# INTech_-_Carte_de_Base.net
KiCad netlist of a schematic drawn in EAGLE
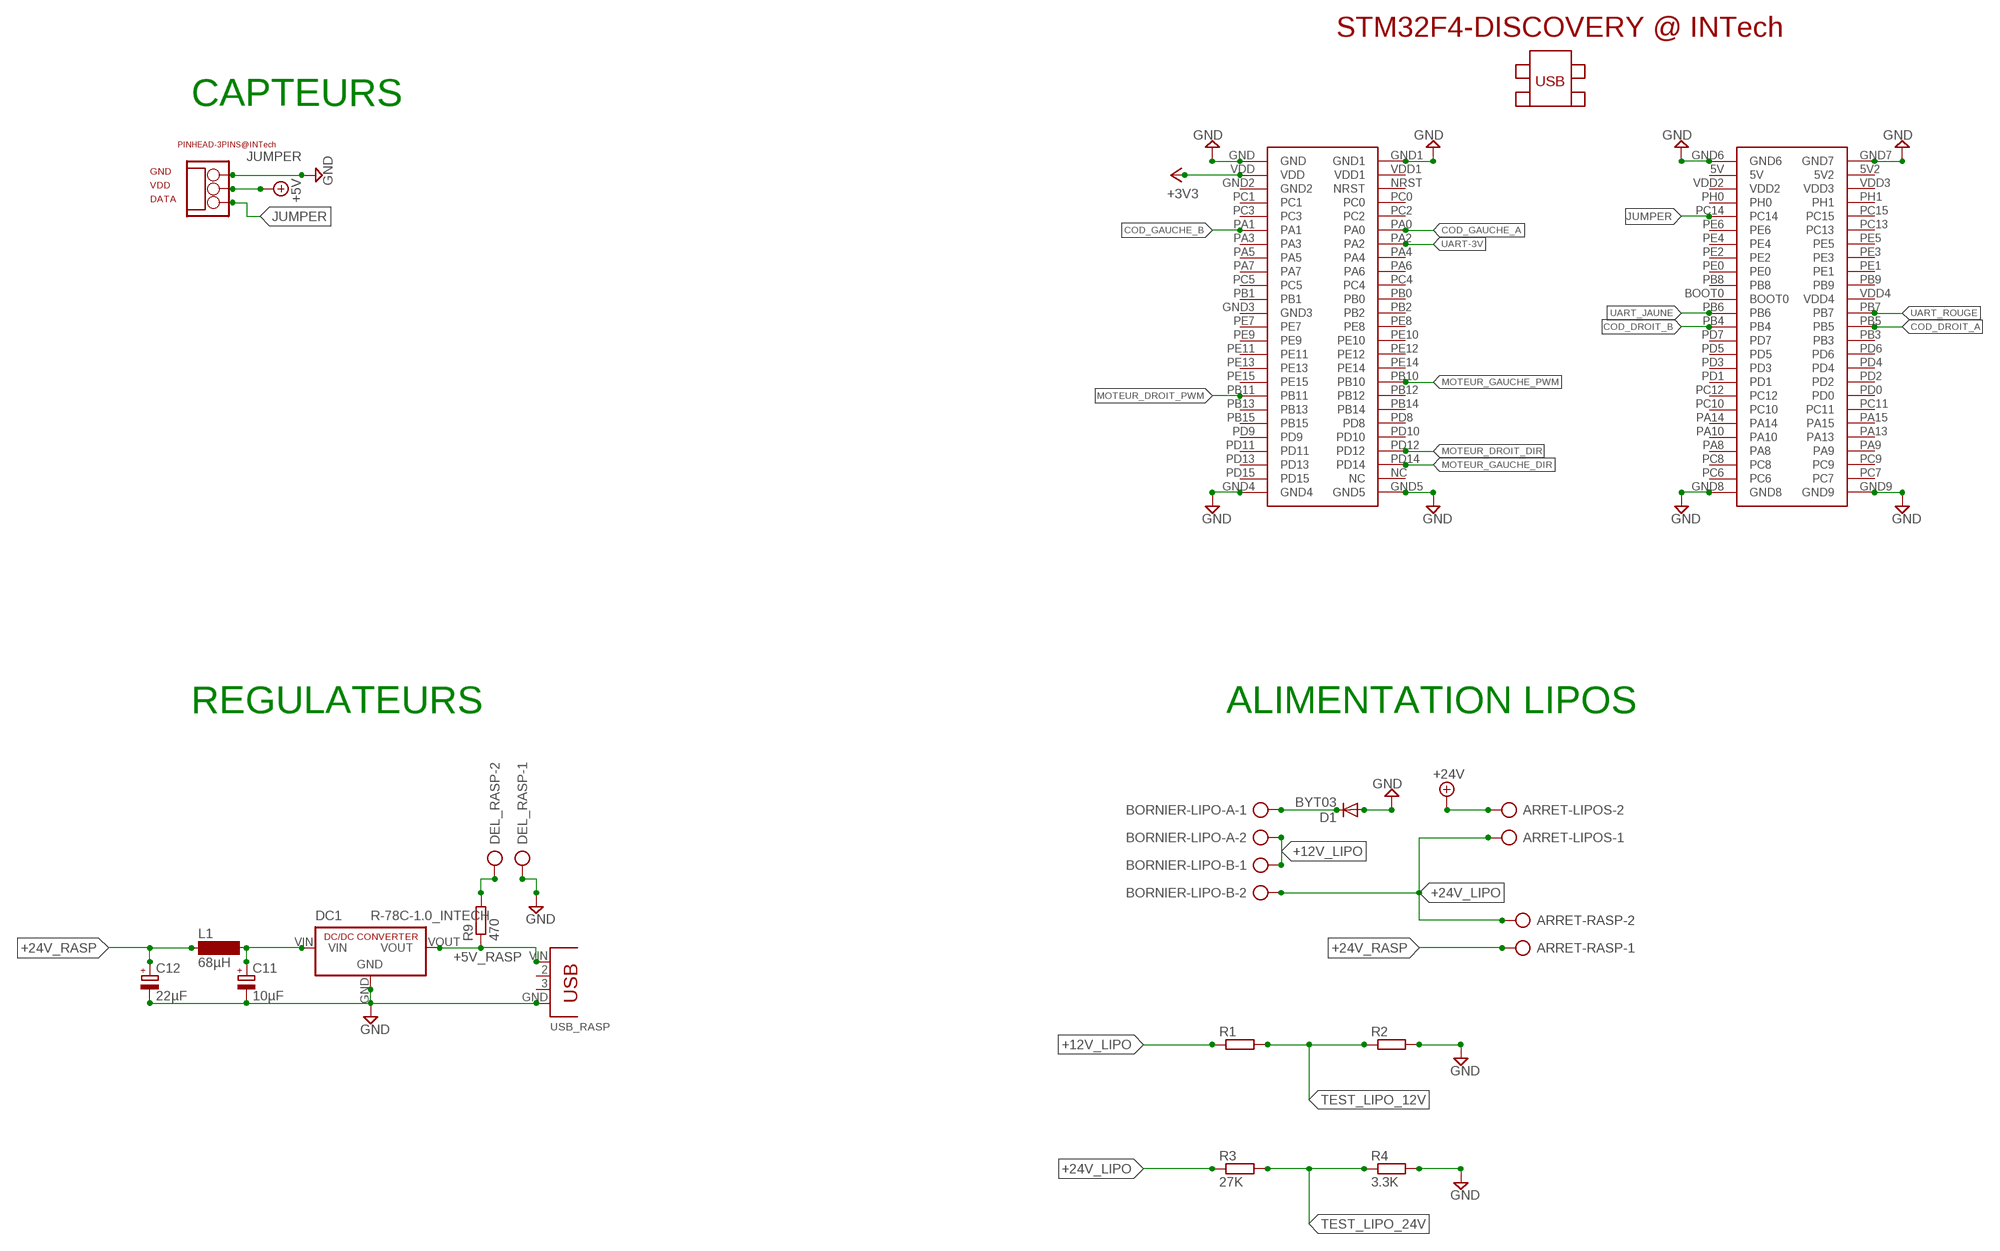
[diagram p0: schematic, sheet 1, part 1 of 2]
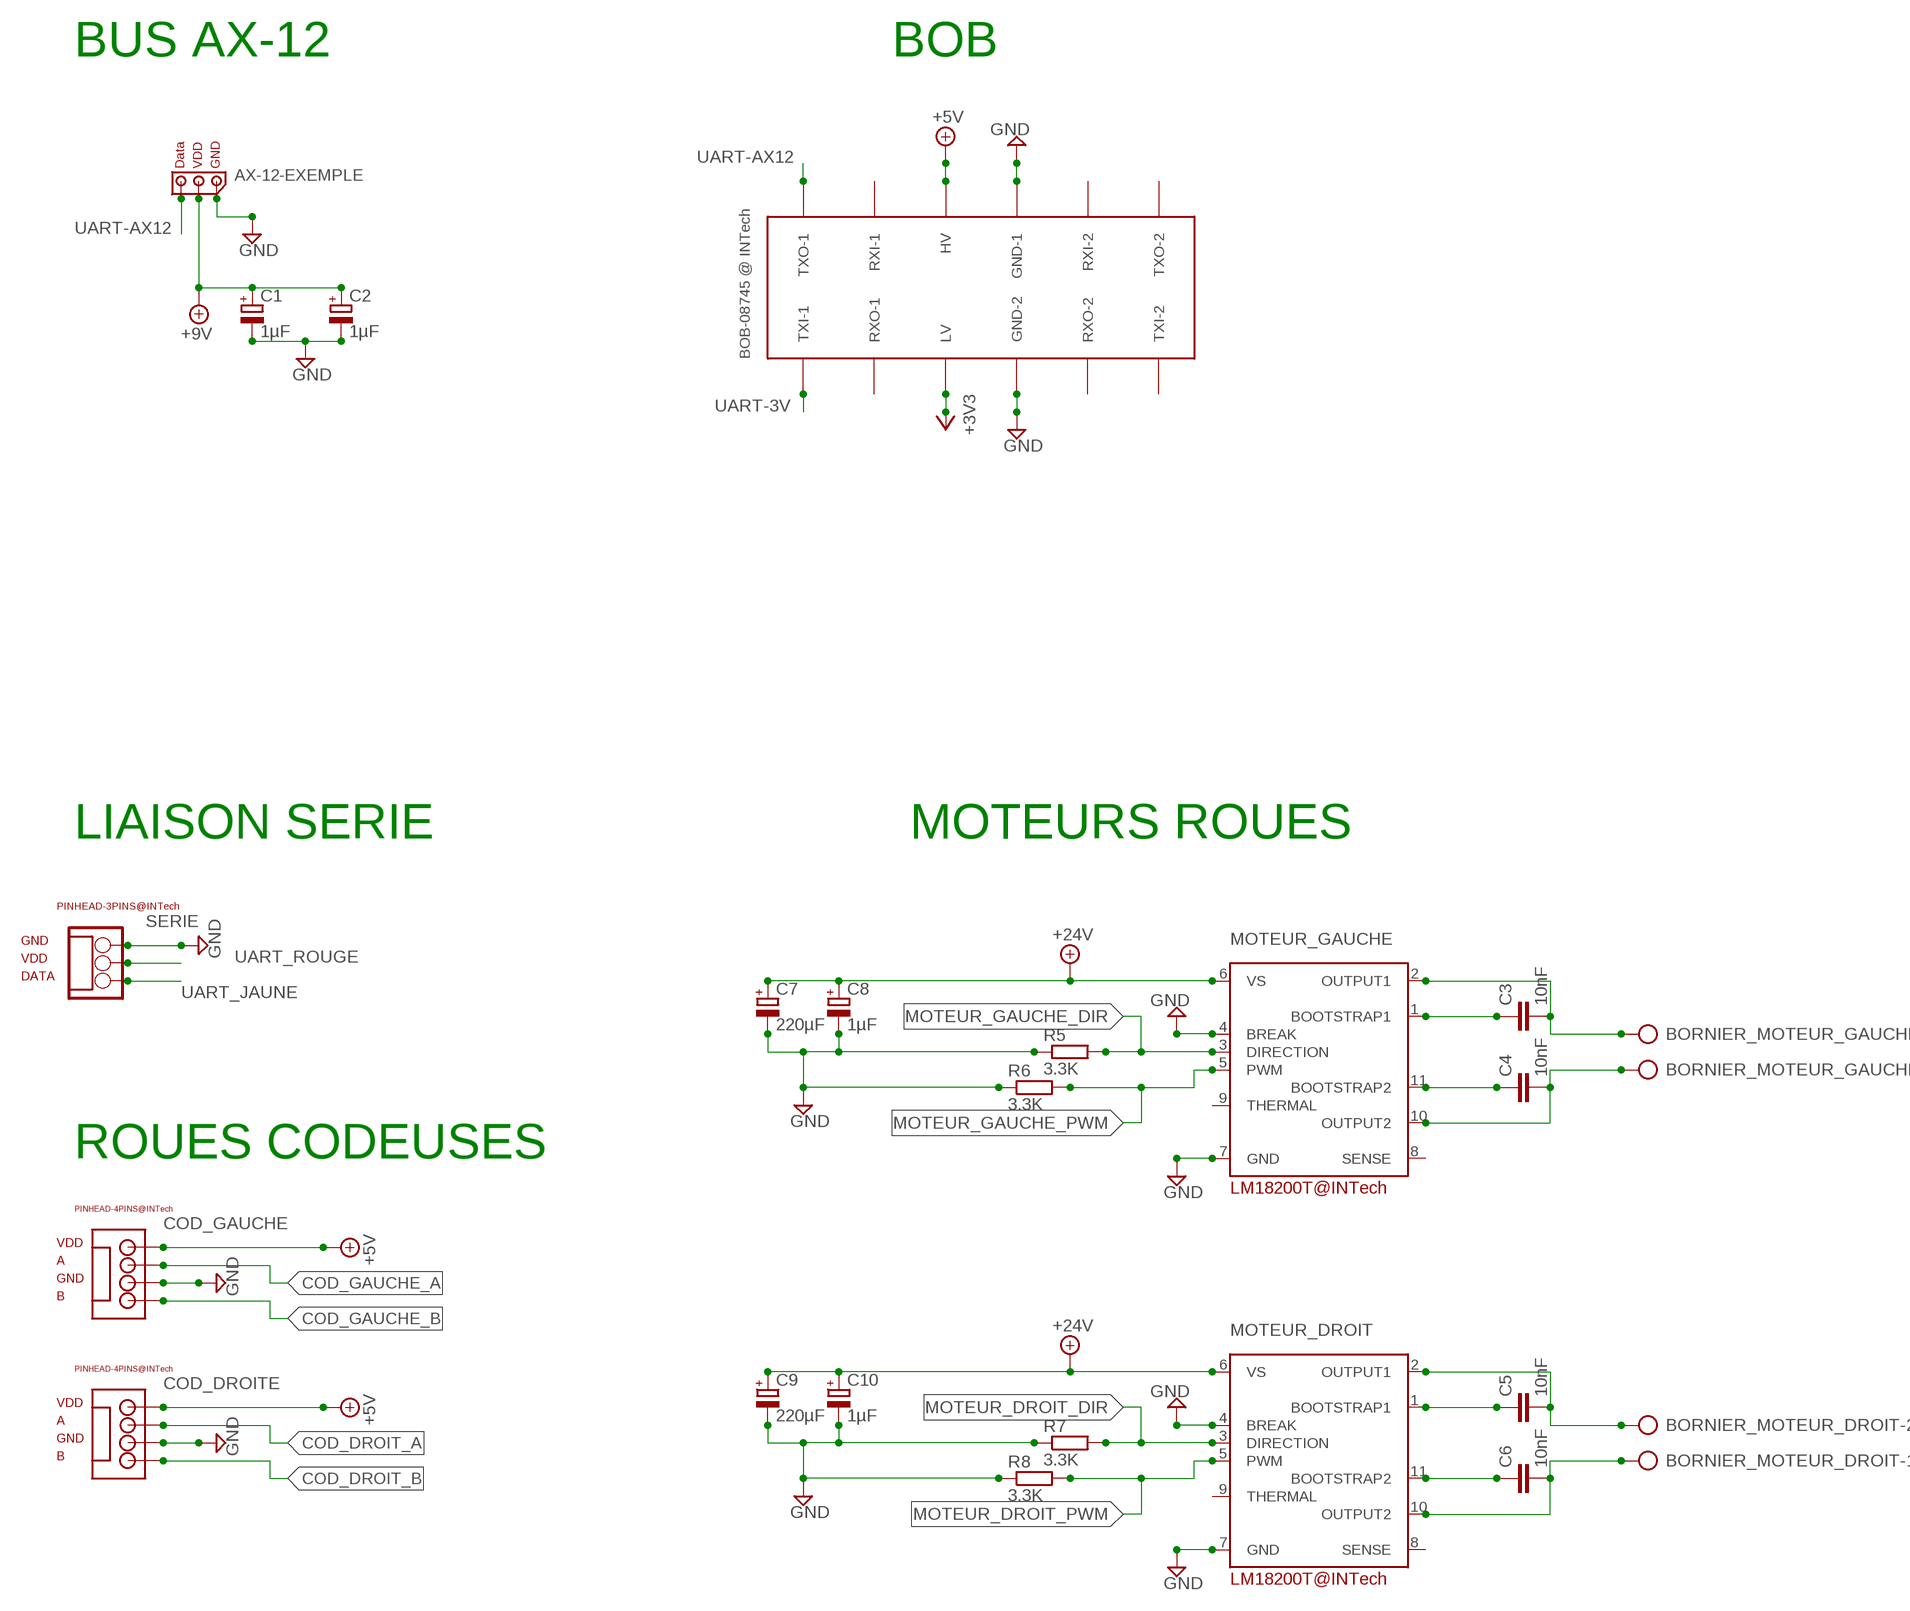
[diagram p1: schematic, sheet 1, part 2 of 2]

(export (version "E")
  (design (tool "Eeschema 10.0.6"))
  (components
    (comp (ref "ARRET-LIPOS")
      (value "AK300/2")
      (footprint "eagle-import:AK300_2")
      (libsource (lib "eagle-import") (part "AK300/2"))
    )
    (comp (ref "ARRET-RASP")
      (value "AK300/2")
      (footprint "eagle-import:AK300_2")
      (libsource (lib "eagle-import") (part "AK300/2"))
    )
    (comp (ref "AX-12-EXEMPLE")
      (value "AX-12_CF_INTECH")
      (footprint "eagle-import:AX-12_CF_INTECH")
      (libsource (lib "eagle-import") (part "AX-12_CF_INTECH"))
    )
    (comp (ref "BORNIER-LIPO-A")
      (value "AK300/2")
      (footprint "eagle-import:AK300_2")
      (libsource (lib "eagle-import") (part "AK300/2"))
    )
    (comp (ref "BORNIER-LIPO-B")
      (value "AK300/2")
      (footprint "eagle-import:AK300_2")
      (libsource (lib "eagle-import") (part "AK300/2"))
    )
    (comp (ref "BORNIER_MOTEUR_DROIT")
      (value "AK300/2")
      (footprint "eagle-import:AK300_2")
      (libsource (lib "eagle-import") (part "AK300/2"))
    )
    (comp (ref "BORNIER_MOTEUR_GAUCHE")
      (value "AK300/2")
      (footprint "eagle-import:AK300_2")
      (libsource (lib "eagle-import") (part "AK300/2"))
    )
    (comp (ref "C1")
      (value "1µF")
      (footprint "eagle-import:E2,5-6E")
      (libsource (lib "eagle-import") (part "CPOL-EUE2,5-6E"))
    )
    (comp (ref "C2")
      (value "1µF")
      (footprint "eagle-import:E2,5-6E")
      (libsource (lib "eagle-import") (part "CPOL-EUE2,5-6E"))
    )
    (comp (ref "C3")
      (value "10nF")
      (footprint "eagle-import:C050-025X075")
      (libsource (lib "eagle-import") (part "C-EU050-025X075"))
    )
    (comp (ref "C4")
      (value "10nF")
      (footprint "eagle-import:C050-025X075")
      (libsource (lib "eagle-import") (part "C-EU050-025X075"))
    )
    (comp (ref "C5")
      (value "10nF")
      (footprint "eagle-import:C050-025X075")
      (libsource (lib "eagle-import") (part "C-EU050-025X075"))
    )
    (comp (ref "C6")
      (value "10nF")
      (footprint "eagle-import:C050-025X075")
      (libsource (lib "eagle-import") (part "C-EU050-025X075"))
    )
    (comp (ref "C7")
      (value "220µF")
      (footprint "eagle-import:E3,5-8")
      (libsource (lib "eagle-import") (part "CPOL-EUE3.5-8"))
    )
    (comp (ref "C8")
      (value "1µF")
      (footprint "eagle-import:E3,5-8")
      (libsource (lib "eagle-import") (part "CPOL-EUE3.5-8"))
    )
    (comp (ref "C9")
      (value "220µF")
      (footprint "eagle-import:E3,5-8")
      (libsource (lib "eagle-import") (part "CPOL-EUE3.5-8"))
    )
    (comp (ref "C10")
      (value "1µF")
      (footprint "eagle-import:E3,5-8")
      (libsource (lib "eagle-import") (part "CPOL-EUE3.5-8"))
    )
    (comp (ref "C11")
      (value "10µF")
      (footprint "eagle-import:E2,5-6")
      (libsource (lib "eagle-import") (part "CPOL-EUE2.5-6"))
    )
    (comp (ref "C12")
      (value "22µF")
      (footprint "eagle-import:E2,5-6")
      (libsource (lib "eagle-import") (part "CPOL-EUE2.5-6"))
    )
    (comp (ref "COD_DROITE")
      (value "PINHEAD-4_CF_INTECH")
      (footprint "eagle-import:PINHEAD-4_CF_INTECH")
      (libsource (lib "eagle-import") (part "PINHEAD-4_CF_INTECH"))
    )
    (comp (ref "COD_GAUCHE")
      (value "PINHEAD-4_CF_INTECH")
      (footprint "eagle-import:PINHEAD-4_CF_INTECH")
      (libsource (lib "eagle-import") (part "PINHEAD-4_CF_INTECH"))
    )
    (comp (ref "D1")
      (value "BYT03")
      (footprint "eagle-import:DO27-15")
      (libsource (lib "eagle-import") (part "BYT03"))
    )
    (comp (ref "DC1")
      (value "R-78C-1.0_INTECH")
      (footprint "eagle-import:SIP3_INTECH")
      (libsource (lib "eagle-import") (part "R-78C-1.0_INTECH"))
    )
    (comp (ref "DEL_RASP")
      (value "AK300/2")
      (footprint "eagle-import:AK300_2")
      (libsource (lib "eagle-import") (part "AK300/2"))
    )
    (comp (ref "JUMPER")
      (value "PINHEAD_CF_INTECH")
      (footprint "eagle-import:PINHEAD_CF_INTECH")
      (libsource (lib "eagle-import") (part "PINHEAD_CF_INTECH"))
    )
    (comp (ref "L1")
      (value "68µH")
      (footprint "eagle-import:SD12K100")
      (libsource (lib "eagle-import") (part "SD12K100"))
    )
    (comp (ref "MOTEUR_DROIT")
      (value "LM18200T_CF_INTECH")
      (footprint "eagle-import:LM18200T_CF_INTECH")
      (libsource (lib "eagle-import") (part "LM18200T_CF_INTECH"))
    )
    (comp (ref "MOTEUR_GAUCHE")
      (value "LM18200T_CF_INTECH")
      (footprint "eagle-import:LM18200T_CF_INTECH")
      (libsource (lib "eagle-import") (part "LM18200T_CF_INTECH"))
    )
    (comp (ref "R1")
      (value "R-EU_0207/10")
      (footprint "eagle-import:0207_10")
      (libsource (lib "eagle-import") (part "R-EU_0207/10"))
    )
    (comp (ref "R2")
      (value "R-EU_0207/10")
      (footprint "eagle-import:0207_10")
      (libsource (lib "eagle-import") (part "R-EU_0207/10"))
    )
    (comp (ref "R3")
      (value "27K")
      (footprint "eagle-import:0207_10")
      (libsource (lib "eagle-import") (part "R-EU_0207/10"))
    )
    (comp (ref "R4")
      (value "3.3K")
      (footprint "eagle-import:0207_10")
      (libsource (lib "eagle-import") (part "R-EU_0207/10"))
    )
    (comp (ref "R5")
      (value "3.3K")
      (footprint "eagle-import:0207_10")
      (libsource (lib "eagle-import") (part "R-EU_0207/10"))
    )
    (comp (ref "R6")
      (value "3.3K")
      (footprint "eagle-import:0207_10")
      (libsource (lib "eagle-import") (part "R-EU_0207/10"))
    )
    (comp (ref "R7")
      (value "3.3K")
      (footprint "eagle-import:0207_10")
      (libsource (lib "eagle-import") (part "R-EU_0207/10"))
    )
    (comp (ref "R8")
      (value "3.3K")
      (footprint "eagle-import:0207_10")
      (libsource (lib "eagle-import") (part "R-EU_0207/10"))
    )
    (comp (ref "R9")
      (value "470")
      (footprint "eagle-import:0204_7")
      (libsource (lib "eagle-import") (part "R-EU_0204/7"))
    )
    (comp (ref "SERIE")
      (value "PINHEAD_CF_INTECH")
      (footprint "eagle-import:PINHEAD_CF_INTECH")
      (libsource (lib "eagle-import") (part "PINHEAD_CF_INTECH"))
    )
    (comp (ref "U$1")
      (value "STM32F4-DISCOVERY")
      (footprint "eagle-import:STM32F4-DISCOVERY")
      (libsource (lib "eagle-import") (part "STM32F4-DISCOVERY"))
    )
    (comp (ref "U$2")
      (value "BOB-08745")
      (footprint "eagle-import:BOB-08745")
      (libsource (lib "eagle-import") (part "BOB-08745"))
    )
    (comp (ref "USB_RASP")
      (value "USB_87520")
      (footprint "eagle-import:USB")
      (libsource (lib "eagle-import") (part "USB_87520"))
    )
  )
  (nets
    (net (code "1") (name "+3V3") (class "Default")
      (node (ref "U$1") (pin "VDD") (pinfunction "VDD_VDD") (pintype "bidirectional"))
      (node (ref "U$2") (pin "LV") (pinfunction "LV_LV") (pintype "bidirectional"))
    )
    (net (code "2") (name "+5V") (class "Default")
      (node (ref "COD_DROITE") (pin "VDD") (pinfunction "VDD_VDD") (pintype "bidirectional"))
      (node (ref "COD_GAUCHE") (pin "VDD") (pinfunction "VDD_VDD") (pintype "bidirectional"))
      (node (ref "JUMPER") (pin "VDD") (pinfunction "VDD_VDD") (pintype "bidirectional"))
      (node (ref "U$2") (pin "HV") (pinfunction "HV_HV") (pintype "bidirectional"))
    )
    (net (code "3") (name "+9V") (class "Default")
      (node (ref "AX-12-EXEMPLE") (pin "VDD") (pinfunction "VDD_VDD") (pintype "passive"))
      (node (ref "C1") (pin "+") (pinfunction "+_+") (pintype "passive"))
      (node (ref "C2") (pin "+") (pinfunction "+_+") (pintype "passive"))
    )
    (net (code "4") (name "+12V_LIPO") (class "Default")
      (node (ref "BORNIER-LIPO-A") (pin "2") (pinfunction "KL_2") (pintype "passive"))
      (node (ref "BORNIER-LIPO-B") (pin "1") (pinfunction "KL_1") (pintype "passive"))
      (node (ref "R1") (pin "1") (pinfunction "1_1") (pintype "passive"))
    )
    (net (code "5") (name "+24V") (class "Default")
      (node (ref "ARRET-LIPOS") (pin "2") (pinfunction "KL_2") (pintype "passive"))
      (node (ref "C10") (pin "+") (pinfunction "+_+") (pintype "passive"))
      (node (ref "C7") (pin "+") (pinfunction "+_+") (pintype "passive"))
      (node (ref "C8") (pin "+") (pinfunction "+_+") (pintype "passive"))
      (node (ref "C9") (pin "+") (pinfunction "+_+") (pintype "passive"))
      (node (ref "MOTEUR_DROIT") (pin "6") (pinfunction "VS_6") (pintype "power_in"))
      (node (ref "MOTEUR_GAUCHE") (pin "6") (pinfunction "VS_6") (pintype "power_in"))
    )
    (net (code "6") (name "+24V_LIPO") (class "Default")
      (node (ref "ARRET-LIPOS") (pin "1") (pinfunction "KL_1") (pintype "passive"))
      (node (ref "ARRET-RASP") (pin "2") (pinfunction "KL_2") (pintype "passive"))
      (node (ref "BORNIER-LIPO-B") (pin "2") (pinfunction "KL_2") (pintype "passive"))
      (node (ref "R3") (pin "1") (pinfunction "1_1") (pintype "passive"))
    )
    (net (code "7") (name "+24V_RASP") (class "Default")
      (node (ref "ARRET-RASP") (pin "1") (pinfunction "KL_1") (pintype "passive"))
      (node (ref "C12") (pin "+") (pinfunction "+_+") (pintype "passive"))
      (node (ref "L1") (pin "1") (pinfunction "1_1") (pintype "passive"))
    )
    (net (code "8") (name "/+5V_RASP") (class "Default")
      (node (ref "DC1") (pin "VOUT") (pinfunction "VOUT_VOUT") (pintype "passive"))
      (node (ref "R9") (pin "1") (pinfunction "1_1") (pintype "passive"))
      (node (ref "USB_RASP") (pin "VIN") (pinfunction "VIN_VIN") (pintype "passive"))
    )
    (net (code "9") (name "/UART-AX12") (class "Default")
      (node (ref "AX-12-EXEMPLE") (pin "DATA") (pinfunction "DATA_DATA") (pintype "passive"))
      (node (ref "U$2") (pin "TXO-1") (pinfunction "TXO-1_TXO-1") (pintype "bidirectional"))
    )
    (net (code "10") (name "COD_DROIT_A") (class "Default")
      (node (ref "COD_DROITE") (pin "A") (pinfunction "A_A") (pintype "bidirectional"))
      (node (ref "U$1") (pin "PB5") (pinfunction "PB5_PB5") (pintype "bidirectional"))
    )
    (net (code "11") (name "COD_DROIT_B") (class "Default")
      (node (ref "COD_DROITE") (pin "B") (pinfunction "B_B") (pintype "bidirectional"))
      (node (ref "U$1") (pin "PB4") (pinfunction "PB4_PB4") (pintype "bidirectional"))
    )
    (net (code "12") (name "COD_GAUCHE_A") (class "Default")
      (node (ref "COD_GAUCHE") (pin "A") (pinfunction "A_A") (pintype "bidirectional"))
      (node (ref "U$1") (pin "PA0") (pinfunction "PA0_PA0") (pintype "bidirectional"))
    )
    (net (code "13") (name "COD_GAUCHE_B") (class "Default")
      (node (ref "COD_GAUCHE") (pin "B") (pinfunction "B_B") (pintype "bidirectional"))
      (node (ref "U$1") (pin "PA1") (pinfunction "PA1_PA1") (pintype "bidirectional"))
    )
    (net (code "14") (name "GND") (class "Default")
      (node (ref "AX-12-EXEMPLE") (pin "GND") (pinfunction "GND_GND") (pintype "passive"))
      (node (ref "C1") (pin "-") (pinfunction "-_-") (pintype "passive"))
      (node (ref "C10") (pin "-") (pinfunction "-_-") (pintype "passive"))
      (node (ref "C11") (pin "-") (pinfunction "-_-") (pintype "passive"))
      (node (ref "C12") (pin "-") (pinfunction "-_-") (pintype "passive"))
      (node (ref "C2") (pin "-") (pinfunction "-_-") (pintype "passive"))
      (node (ref "C7") (pin "-") (pinfunction "-_-") (pintype "passive"))
      (node (ref "C8") (pin "-") (pinfunction "-_-") (pintype "passive"))
      (node (ref "C9") (pin "-") (pinfunction "-_-") (pintype "passive"))
      (node (ref "COD_DROITE") (pin "GND") (pinfunction "GND_GND") (pintype "bidirectional"))
      (node (ref "COD_GAUCHE") (pin "GND") (pinfunction "GND_GND") (pintype "bidirectional"))
      (node (ref "D1") (pin "A") (pinfunction "A_A") (pintype "passive"))
      (node (ref "DC1") (pin "GND") (pinfunction "GND_GND") (pintype "passive"))
      (node (ref "DEL_RASP") (pin "1") (pinfunction "KL_1") (pintype "passive"))
      (node (ref "JUMPER") (pin "GND") (pinfunction "GND_GND") (pintype "bidirectional"))
      (node (ref "MOTEUR_DROIT") (pin "4") (pinfunction "BREAK_4") (pintype "input"))
      (node (ref "MOTEUR_DROIT") (pin "7") (pinfunction "GND_7") (pintype "power_in"))
      (node (ref "MOTEUR_GAUCHE") (pin "4") (pinfunction "BREAK_4") (pintype "input"))
      (node (ref "MOTEUR_GAUCHE") (pin "7") (pinfunction "GND_7") (pintype "power_in"))
      (node (ref "R2") (pin "2") (pinfunction "2_2") (pintype "passive"))
      (node (ref "R4") (pin "2") (pinfunction "2_2") (pintype "passive"))
      (node (ref "R5") (pin "1") (pinfunction "1_1") (pintype "passive"))
      (node (ref "R6") (pin "1") (pinfunction "1_1") (pintype "passive"))
      (node (ref "R7") (pin "1") (pinfunction "1_1") (pintype "passive"))
      (node (ref "R8") (pin "1") (pinfunction "1_1") (pintype "passive"))
      (node (ref "SERIE") (pin "GND") (pinfunction "GND_GND") (pintype "bidirectional"))
      (node (ref "U$1") (pin "GND") (pinfunction "GND_GND") (pintype "bidirectional"))
      (node (ref "U$1") (pin "GND1") (pinfunction "GND1_GND1") (pintype "bidirectional"))
      (node (ref "U$1") (pin "GND4") (pinfunction "GND4_GND4") (pintype "bidirectional"))
      (node (ref "U$1") (pin "GND5") (pinfunction "GND5_GND5") (pintype "bidirectional"))
      (node (ref "U$1") (pin "GND6") (pinfunction "GND6_GND6") (pintype "bidirectional"))
      (node (ref "U$1") (pin "GND7") (pinfunction "GND7_GND7") (pintype "bidirectional"))
      (node (ref "U$1") (pin "GND8") (pinfunction "GND8_GND8") (pintype "bidirectional"))
      (node (ref "U$1") (pin "GND9") (pinfunction "GND9_GND9") (pintype "bidirectional"))
      (node (ref "U$2") (pin "GND-1") (pinfunction "GND-1_GND-1") (pintype "bidirectional"))
      (node (ref "U$2") (pin "GND-2") (pinfunction "GND-2_GND-2") (pintype "bidirectional"))
      (node (ref "USB_RASP") (pin "GND") (pinfunction "GND_GND") (pintype "passive"))
    )
    (net (code "15") (name "JUMPER") (class "Default")
      (node (ref "JUMPER") (pin "DATA") (pinfunction "DATA_DATA") (pintype "bidirectional"))
      (node (ref "U$1") (pin "PC14") (pinfunction "PC14_PC14") (pintype "bidirectional"))
    )
    (net (code "16") (name "MOTEUR_DROIT_DIR") (class "Default")
      (node (ref "MOTEUR_DROIT") (pin "3") (pinfunction "DIRECTION_3") (pintype "input"))
      (node (ref "R7") (pin "2") (pinfunction "2_2") (pintype "passive"))
      (node (ref "U$1") (pin "PD12") (pinfunction "PD12_PD12") (pintype "bidirectional"))
    )
    (net (code "17") (name "MOTEUR_DROIT_PWM") (class "Default")
      (node (ref "MOTEUR_DROIT") (pin "5") (pinfunction "PWM_5") (pintype "input"))
      (node (ref "R8") (pin "2") (pinfunction "2_2") (pintype "passive"))
      (node (ref "U$1") (pin "PB11") (pinfunction "PB11_PB11") (pintype "bidirectional"))
    )
    (net (code "18") (name "MOTEUR_GAUCHE_DIR") (class "Default")
      (node (ref "MOTEUR_GAUCHE") (pin "3") (pinfunction "DIRECTION_3") (pintype "input"))
      (node (ref "R5") (pin "2") (pinfunction "2_2") (pintype "passive"))
      (node (ref "U$1") (pin "PD14") (pinfunction "PD14_PD14") (pintype "bidirectional"))
    )
    (net (code "19") (name "MOTEUR_GAUCHE_PWM") (class "Default")
      (node (ref "MOTEUR_GAUCHE") (pin "5") (pinfunction "PWM_5") (pintype "input"))
      (node (ref "R6") (pin "2") (pinfunction "2_2") (pintype "passive"))
      (node (ref "U$1") (pin "PB10") (pinfunction "PB10_PB10") (pintype "bidirectional"))
    )
    (net (code "20") (name "Net-(BORNIER-LIPO-AA-KL)") (class "Default")
      (node (ref "BORNIER-LIPO-A") (pin "1") (pinfunction "KL_1") (pintype "passive"))
      (node (ref "D1") (pin "C") (pinfunction "C_C") (pintype "passive"))
    )
    (net (code "21") (name "Net-(BORNIER_MOTEUR_DROITA-KL)") (class "Default")
      (node (ref "BORNIER_MOTEUR_DROIT") (pin "1") (pinfunction "KL_1") (pintype "passive"))
      (node (ref "C6") (pin "2") (pinfunction "2_2") (pintype "passive"))
      (node (ref "MOTEUR_DROIT") (pin "10") (pinfunction "OUTPUT2_10") (pintype "output"))
    )
    (net (code "22") (name "Net-(BORNIER_MOTEUR_DROITB-KL)") (class "Default")
      (node (ref "BORNIER_MOTEUR_DROIT") (pin "2") (pinfunction "KL_2") (pintype "passive"))
      (node (ref "C5") (pin "2") (pinfunction "2_2") (pintype "passive"))
      (node (ref "MOTEUR_DROIT") (pin "2") (pinfunction "OUTPUT1_2") (pintype "output"))
    )
    (net (code "23") (name "Net-(BORNIER_MOTEUR_GAUCHEA-KL)") (class "Default")
      (node (ref "BORNIER_MOTEUR_GAUCHE") (pin "1") (pinfunction "KL_1") (pintype "passive"))
      (node (ref "C4") (pin "2") (pinfunction "2_2") (pintype "passive"))
      (node (ref "MOTEUR_GAUCHE") (pin "10") (pinfunction "OUTPUT2_10") (pintype "output"))
    )
    (net (code "24") (name "Net-(BORNIER_MOTEUR_GAUCHEB-KL)") (class "Default")
      (node (ref "BORNIER_MOTEUR_GAUCHE") (pin "2") (pinfunction "KL_2") (pintype "passive"))
      (node (ref "C3") (pin "2") (pinfunction "2_2") (pintype "passive"))
      (node (ref "MOTEUR_GAUCHE") (pin "2") (pinfunction "OUTPUT1_2") (pintype "output"))
    )
    (net (code "25") (name "Net-(C11-Pad+)") (class "Default")
      (node (ref "C11") (pin "+") (pinfunction "+_+") (pintype "passive"))
      (node (ref "DC1") (pin "VIN") (pinfunction "VIN_VIN") (pintype "passive"))
      (node (ref "L1") (pin "2") (pinfunction "2_2") (pintype "passive"))
    )
    (net (code "26") (name "Net-(DEL_RASPB-KL)") (class "Default")
      (node (ref "DEL_RASP") (pin "2") (pinfunction "KL_2") (pintype "passive"))
      (node (ref "R9") (pin "2") (pinfunction "2_2") (pintype "passive"))
    )
    (net (code "27") (name "Net-(MOTEUR_DROIT-BOOTSTRAP1)") (class "Default")
      (node (ref "C5") (pin "1") (pinfunction "1_1") (pintype "passive"))
      (node (ref "MOTEUR_DROIT") (pin "1") (pinfunction "BOOTSTRAP1_1") (pintype "input"))
    )
    (net (code "28") (name "Net-(MOTEUR_DROIT-BOOTSTRAP2)") (class "Default")
      (node (ref "C6") (pin "1") (pinfunction "1_1") (pintype "passive"))
      (node (ref "MOTEUR_DROIT") (pin "11") (pinfunction "BOOTSTRAP2_11") (pintype "input"))
    )
    (net (code "29") (name "Net-(MOTEUR_GAUCHE-BOOTSTRAP1)") (class "Default")
      (node (ref "C3") (pin "1") (pinfunction "1_1") (pintype "passive"))
      (node (ref "MOTEUR_GAUCHE") (pin "1") (pinfunction "BOOTSTRAP1_1") (pintype "input"))
    )
    (net (code "30") (name "Net-(MOTEUR_GAUCHE-BOOTSTRAP2)") (class "Default")
      (node (ref "C4") (pin "1") (pinfunction "1_1") (pintype "passive"))
      (node (ref "MOTEUR_GAUCHE") (pin "11") (pinfunction "BOOTSTRAP2_11") (pintype "input"))
    )
    (net (code "31") (name "TEST_LIPO_12V") (class "Default")
      (node (ref "R1") (pin "2") (pinfunction "2_2") (pintype "passive"))
      (node (ref "R2") (pin "1") (pinfunction "1_1") (pintype "passive"))
    )
    (net (code "32") (name "TEST_LIPO_24V") (class "Default")
      (node (ref "R3") (pin "2") (pinfunction "2_2") (pintype "passive"))
      (node (ref "R4") (pin "1") (pinfunction "1_1") (pintype "passive"))
    )
    (net (code "33") (name "UART-3V") (class "Default")
      (node (ref "U$1") (pin "PA2") (pinfunction "PA2_PA2") (pintype "bidirectional"))
      (node (ref "U$2") (pin "TXI-1") (pinfunction "TXI-1_TXI-1") (pintype "bidirectional"))
    )
    (net (code "34") (name "UART_JAUNE") (class "Default")
      (node (ref "SERIE") (pin "DATA") (pinfunction "DATA_DATA") (pintype "bidirectional"))
      (node (ref "U$1") (pin "PB6") (pinfunction "PB6_PB6") (pintype "bidirectional"))
    )
    (net (code "35") (name "UART_ROUGE") (class "Default")
      (node (ref "SERIE") (pin "VDD") (pinfunction "VDD_VDD") (pintype "bidirectional"))
      (node (ref "U$1") (pin "PB7") (pinfunction "PB7_PB7") (pintype "bidirectional"))
    )
    (net (code "36") (name "unconnected-(MOTEUR_DROIT-SENSE-Pad8)") (class "Default")
      (node (ref "MOTEUR_DROIT") (pin "8") (pinfunction "SENSE_8") (pintype "output"))
    )
    (net (code "37") (name "unconnected-(MOTEUR_DROIT-THERMAL-Pad9)") (class "Default")
      (node (ref "MOTEUR_DROIT") (pin "9") (pinfunction "THERMAL_9") (pintype "output"))
    )
    (net (code "38") (name "unconnected-(MOTEUR_GAUCHE-SENSE-Pad8)") (class "Default")
      (node (ref "MOTEUR_GAUCHE") (pin "8") (pinfunction "SENSE_8") (pintype "output"))
    )
    (net (code "39") (name "unconnected-(MOTEUR_GAUCHE-THERMAL-Pad9)") (class "Default")
      (node (ref "MOTEUR_GAUCHE") (pin "9") (pinfunction "THERMAL_9") (pintype "output"))
    )
    (net (code "40") (name "unconnected-(U$1-Pad5V)") (class "Default")
      (node (ref "U$1") (pin "5V") (pinfunction "5V_5V") (pintype "bidirectional"))
    )
    (net (code "41") (name "unconnected-(U$1-Pad5V2)") (class "Default")
      (node (ref "U$1") (pin "5V2") (pinfunction "5V2_5V2") (pintype "bidirectional"))
    )
    (net (code "42") (name "unconnected-(U$1-PadBOOT0)") (class "Default")
      (node (ref "U$1") (pin "BOOT0") (pinfunction "BOOT0_BOOT0") (pintype "bidirectional"))
    )
    (net (code "43") (name "unconnected-(U$1-PadGND2)") (class "Default")
      (node (ref "U$1") (pin "GND2") (pinfunction "GND2_GND2") (pintype "bidirectional"))
    )
    (net (code "44") (name "unconnected-(U$1-PadGND3)") (class "Default")
      (node (ref "U$1") (pin "GND3") (pinfunction "GND3_GND3") (pintype "bidirectional"))
    )
    (net (code "45") (name "unconnected-(U$1-PadNC)") (class "Default")
      (node (ref "U$1") (pin "NC") (pinfunction "NC_NC") (pintype "bidirectional"))
    )
    (net (code "46") (name "unconnected-(U$1-PadNRST)") (class "Default")
      (node (ref "U$1") (pin "NRST") (pinfunction "NRST_NRST") (pintype "bidirectional"))
    )
    (net (code "47") (name "unconnected-(U$1-PadPA3)") (class "Default")
      (node (ref "U$1") (pin "PA3") (pinfunction "PA3_PA3") (pintype "bidirectional"))
    )
    (net (code "48") (name "unconnected-(U$1-PadPA4)") (class "Default")
      (node (ref "U$1") (pin "PA4") (pinfunction "PA4_PA4") (pintype "bidirectional"))
    )
    (net (code "49") (name "unconnected-(U$1-PadPA5)") (class "Default")
      (node (ref "U$1") (pin "PA5") (pinfunction "PA5_PA5") (pintype "bidirectional"))
    )
    (net (code "50") (name "unconnected-(U$1-PadPA6)") (class "Default")
      (node (ref "U$1") (pin "PA6") (pinfunction "PA6_PA6") (pintype "bidirectional"))
    )
    (net (code "51") (name "unconnected-(U$1-PadPA7)") (class "Default")
      (node (ref "U$1") (pin "PA7") (pinfunction "PA7_PA7") (pintype "bidirectional"))
    )
    (net (code "52") (name "unconnected-(U$1-PadPA8)") (class "Default")
      (node (ref "U$1") (pin "PA8") (pinfunction "PA8_PA8") (pintype "bidirectional"))
    )
    (net (code "53") (name "unconnected-(U$1-PadPA9)") (class "Default")
      (node (ref "U$1") (pin "PA9") (pinfunction "PA9_PA9") (pintype "bidirectional"))
    )
    (net (code "54") (name "unconnected-(U$1-PadPA10)") (class "Default")
      (node (ref "U$1") (pin "PA10") (pinfunction "PA10_PA10") (pintype "bidirectional"))
    )
    (net (code "55") (name "unconnected-(U$1-PadPA13)") (class "Default")
      (node (ref "U$1") (pin "PA13") (pinfunction "PA13_PA13") (pintype "bidirectional"))
    )
    (net (code "56") (name "unconnected-(U$1-PadPA14)") (class "Default")
      (node (ref "U$1") (pin "PA14") (pinfunction "PA14_PA14") (pintype "bidirectional"))
    )
    (net (code "57") (name "unconnected-(U$1-PadPA15)") (class "Default")
      (node (ref "U$1") (pin "PA15") (pinfunction "PA15_PA15") (pintype "bidirectional"))
    )
    (net (code "58") (name "unconnected-(U$1-PadPB0)") (class "Default")
      (node (ref "U$1") (pin "PB0") (pinfunction "PB0_PB0") (pintype "bidirectional"))
    )
    (net (code "59") (name "unconnected-(U$1-PadPB1)") (class "Default")
      (node (ref "U$1") (pin "PB1") (pinfunction "PB1_PB1") (pintype "bidirectional"))
    )
    (net (code "60") (name "unconnected-(U$1-PadPB2)") (class "Default")
      (node (ref "U$1") (pin "PB2") (pinfunction "PB2_PB2") (pintype "bidirectional"))
    )
    (net (code "61") (name "unconnected-(U$1-PadPB3)") (class "Default")
      (node (ref "U$1") (pin "PB3") (pinfunction "PB3_PB3") (pintype "bidirectional"))
    )
    (net (code "62") (name "unconnected-(U$1-PadPB8)") (class "Default")
      (node (ref "U$1") (pin "PB8") (pinfunction "PB8_PB8") (pintype "bidirectional"))
    )
    (net (code "63") (name "unconnected-(U$1-PadPB9)") (class "Default")
      (node (ref "U$1") (pin "PB9") (pinfunction "PB9_PB9") (pintype "bidirectional"))
    )
    (net (code "64") (name "unconnected-(U$1-PadPB12)") (class "Default")
      (node (ref "U$1") (pin "PB12") (pinfunction "PB12_PB12") (pintype "bidirectional"))
    )
    (net (code "65") (name "unconnected-(U$1-PadPB13)") (class "Default")
      (node (ref "U$1") (pin "PB13") (pinfunction "PB13_PB13") (pintype "bidirectional"))
    )
    (net (code "66") (name "unconnected-(U$1-PadPB14)") (class "Default")
      (node (ref "U$1") (pin "PB14") (pinfunction "PB14_PB14") (pintype "bidirectional"))
    )
    (net (code "67") (name "unconnected-(U$1-PadPB15)") (class "Default")
      (node (ref "U$1") (pin "PB15") (pinfunction "PB15_PB15") (pintype "bidirectional"))
    )
    (net (code "68") (name "unconnected-(U$1-PadPC0)") (class "Default")
      (node (ref "U$1") (pin "PC0") (pinfunction "PC0_PC0") (pintype "bidirectional"))
    )
    (net (code "69") (name "unconnected-(U$1-PadPC1)") (class "Default")
      (node (ref "U$1") (pin "PC1") (pinfunction "PC1_PC1") (pintype "bidirectional"))
    )
    (net (code "70") (name "unconnected-(U$1-PadPC2)") (class "Default")
      (node (ref "U$1") (pin "PC2") (pinfunction "PC2_PC2") (pintype "bidirectional"))
    )
    (net (code "71") (name "unconnected-(U$1-PadPC3)") (class "Default")
      (node (ref "U$1") (pin "PC3") (pinfunction "PC3_PC3") (pintype "bidirectional"))
    )
    (net (code "72") (name "unconnected-(U$1-PadPC4)") (class "Default")
      (node (ref "U$1") (pin "PC4") (pinfunction "PC4_PC4") (pintype "bidirectional"))
    )
    (net (code "73") (name "unconnected-(U$1-PadPC5)") (class "Default")
      (node (ref "U$1") (pin "PC5") (pinfunction "PC5_PC5") (pintype "bidirectional"))
    )
    (net (code "74") (name "unconnected-(U$1-PadPC6)") (class "Default")
      (node (ref "U$1") (pin "PC6") (pinfunction "PC6_PC6") (pintype "bidirectional"))
    )
    (net (code "75") (name "unconnected-(U$1-PadPC7)") (class "Default")
      (node (ref "U$1") (pin "PC7") (pinfunction "PC7_PC7") (pintype "bidirectional"))
    )
    (net (code "76") (name "unconnected-(U$1-PadPC8)") (class "Default")
      (node (ref "U$1") (pin "PC8") (pinfunction "PC8_PC8") (pintype "bidirectional"))
    )
    (net (code "77") (name "unconnected-(U$1-PadPC9)") (class "Default")
      (node (ref "U$1") (pin "PC9") (pinfunction "PC9_PC9") (pintype "bidirectional"))
    )
    (net (code "78") (name "unconnected-(U$1-PadPC10)") (class "Default")
      (node (ref "U$1") (pin "PC10") (pinfunction "PC10_PC10") (pintype "bidirectional"))
    )
    (net (code "79") (name "unconnected-(U$1-PadPC11)") (class "Default")
      (node (ref "U$1") (pin "PC11") (pinfunction "PC11_PC11") (pintype "bidirectional"))
    )
    (net (code "80") (name "unconnected-(U$1-PadPC12)") (class "Default")
      (node (ref "U$1") (pin "PC12") (pinfunction "PC12_PC12") (pintype "bidirectional"))
    )
    (net (code "81") (name "unconnected-(U$1-PadPC13)") (class "Default")
      (node (ref "U$1") (pin "PC13") (pinfunction "PC13_PC13") (pintype "bidirectional"))
    )
    (net (code "82") (name "unconnected-(U$1-PadPC15)") (class "Default")
      (node (ref "U$1") (pin "PC15") (pinfunction "PC15_PC15") (pintype "bidirectional"))
    )
    (net (code "83") (name "unconnected-(U$1-PadPD0)") (class "Default")
      (node (ref "U$1") (pin "PD0") (pinfunction "PD0_PD0") (pintype "bidirectional"))
    )
    (net (code "84") (name "unconnected-(U$1-PadPD1)") (class "Default")
      (node (ref "U$1") (pin "PD1") (pinfunction "PD1_PD1") (pintype "bidirectional"))
    )
    (net (code "85") (name "unconnected-(U$1-PadPD2)") (class "Default")
      (node (ref "U$1") (pin "PD2") (pinfunction "PD2_PD2") (pintype "bidirectional"))
    )
    (net (code "86") (name "unconnected-(U$1-PadPD3)") (class "Default")
      (node (ref "U$1") (pin "PD3") (pinfunction "PD3_PD3") (pintype "bidirectional"))
    )
    (net (code "87") (name "unconnected-(U$1-PadPD4)") (class "Default")
      (node (ref "U$1") (pin "PD4") (pinfunction "PD4_PD4") (pintype "bidirectional"))
    )
    (net (code "88") (name "unconnected-(U$1-PadPD5)") (class "Default")
      (node (ref "U$1") (pin "PD5") (pinfunction "PD5_PD5") (pintype "bidirectional"))
    )
    (net (code "89") (name "unconnected-(U$1-PadPD6)") (class "Default")
      (node (ref "U$1") (pin "PD6") (pinfunction "PD6_PD6") (pintype "bidirectional"))
    )
    (net (code "90") (name "unconnected-(U$1-PadPD7)") (class "Default")
      (node (ref "U$1") (pin "PD7") (pinfunction "PD7_PD7") (pintype "bidirectional"))
    )
    (net (code "91") (name "unconnected-(U$1-PadPD8)") (class "Default")
      (node (ref "U$1") (pin "PD8") (pinfunction "PD8_PD8") (pintype "bidirectional"))
    )
    (net (code "92") (name "unconnected-(U$1-PadPD9)") (class "Default")
      (node (ref "U$1") (pin "PD9") (pinfunction "PD9_PD9") (pintype "bidirectional"))
    )
    (net (code "93") (name "unconnected-(U$1-PadPD10)") (class "Default")
      (node (ref "U$1") (pin "PD10") (pinfunction "PD10_PD10") (pintype "bidirectional"))
    )
    (net (code "94") (name "unconnected-(U$1-PadPD11)") (class "Default")
      (node (ref "U$1") (pin "PD11") (pinfunction "PD11_PD11") (pintype "bidirectional"))
    )
    (net (code "95") (name "unconnected-(U$1-PadPD13)") (class "Default")
      (node (ref "U$1") (pin "PD13") (pinfunction "PD13_PD13") (pintype "bidirectional"))
    )
    (net (code "96") (name "unconnected-(U$1-PadPD15)") (class "Default")
      (node (ref "U$1") (pin "PD15") (pinfunction "PD15_PD15") (pintype "bidirectional"))
    )
    (net (code "97") (name "unconnected-(U$1-PadPE0)") (class "Default")
      (node (ref "U$1") (pin "PE0") (pinfunction "PE0_PE0") (pintype "bidirectional"))
    )
    (net (code "98") (name "unconnected-(U$1-PadPE1)") (class "Default")
      (node (ref "U$1") (pin "PE1") (pinfunction "PE1_PE1") (pintype "bidirectional"))
    )
    (net (code "99") (name "unconnected-(U$1-PadPE2)") (class "Default")
      (node (ref "U$1") (pin "PE2") (pinfunction "PE2_PE2") (pintype "bidirectional"))
    )
    (net (code "100") (name "unconnected-(U$1-PadPE3)") (class "Default")
      (node (ref "U$1") (pin "PE3") (pinfunction "PE3_PE3") (pintype "bidirectional"))
    )
    (net (code "101") (name "unconnected-(U$1-PadPE4)") (class "Default")
      (node (ref "U$1") (pin "PE4") (pinfunction "PE4_PE4") (pintype "bidirectional"))
    )
    (net (code "102") (name "unconnected-(U$1-PadPE5)") (class "Default")
      (node (ref "U$1") (pin "PE5") (pinfunction "PE5_PE5") (pintype "bidirectional"))
    )
    (net (code "103") (name "unconnected-(U$1-PadPE6)") (class "Default")
      (node (ref "U$1") (pin "PE6") (pinfunction "PE6_PE6") (pintype "bidirectional"))
    )
    (net (code "104") (name "unconnected-(U$1-PadPE7)") (class "Default")
      (node (ref "U$1") (pin "PE7") (pinfunction "PE7_PE7") (pintype "bidirectional"))
    )
    (net (code "105") (name "unconnected-(U$1-PadPE8)") (class "Default")
      (node (ref "U$1") (pin "PE8") (pinfunction "PE8_PE8") (pintype "bidirectional"))
    )
    (net (code "106") (name "unconnected-(U$1-PadPE9)") (class "Default")
      (node (ref "U$1") (pin "PE9") (pinfunction "PE9_PE9") (pintype "bidirectional"))
    )
    (net (code "107") (name "unconnected-(U$1-PadPE10)") (class "Default")
      (node (ref "U$1") (pin "PE10") (pinfunction "PE10_PE10") (pintype "bidirectional"))
    )
    (net (code "108") (name "unconnected-(U$1-PadPE11)") (class "Default")
      (node (ref "U$1") (pin "PE11") (pinfunction "PE11_PE11") (pintype "bidirectional"))
    )
    (net (code "109") (name "unconnected-(U$1-PadPE12)") (class "Default")
      (node (ref "U$1") (pin "PE12") (pinfunction "PE12_PE12") (pintype "bidirectional"))
    )
    (net (code "110") (name "unconnected-(U$1-PadPE13)") (class "Default")
      (node (ref "U$1") (pin "PE13") (pinfunction "PE13_PE13") (pintype "bidirectional"))
    )
    (net (code "111") (name "unconnected-(U$1-PadPE14)") (class "Default")
      (node (ref "U$1") (pin "PE14") (pinfunction "PE14_PE14") (pintype "bidirectional"))
    )
    (net (code "112") (name "unconnected-(U$1-PadPE15)") (class "Default")
      (node (ref "U$1") (pin "PE15") (pinfunction "PE15_PE15") (pintype "bidirectional"))
    )
    (net (code "113") (name "unconnected-(U$1-PadPH0)") (class "Default")
      (node (ref "U$1") (pin "PH0") (pinfunction "PH0_PH0") (pintype "bidirectional"))
    )
    (net (code "114") (name "unconnected-(U$1-PadPH1)") (class "Default")
      (node (ref "U$1") (pin "PH1") (pinfunction "PH1_PH1") (pintype "bidirectional"))
    )
    (net (code "115") (name "unconnected-(U$1-PadVDD1)") (class "Default")
      (node (ref "U$1") (pin "VDD1") (pinfunction "VDD1_VDD1") (pintype "bidirectional"))
    )
    (net (code "116") (name "unconnected-(U$1-PadVDD2)") (class "Default")
      (node (ref "U$1") (pin "VDD2") (pinfunction "VDD2_VDD2") (pintype "bidirectional"))
    )
    (net (code "117") (name "unconnected-(U$1-PadVDD3)") (class "Default")
      (node (ref "U$1") (pin "VDD3") (pinfunction "VDD3_VDD3") (pintype "bidirectional"))
    )
    (net (code "118") (name "unconnected-(U$1-PadVDD4)") (class "Default")
      (node (ref "U$1") (pin "VDD4") (pinfunction "VDD4_VDD4") (pintype "bidirectional"))
    )
    (net (code "119") (name "unconnected-(U$2-PadRXI-1)") (class "Default")
      (node (ref "U$2") (pin "RXI-1") (pinfunction "RXI-1_RXI-1") (pintype "bidirectional"))
    )
    (net (code "120") (name "unconnected-(U$2-PadRXI-2)") (class "Default")
      (node (ref "U$2") (pin "RXI-2") (pinfunction "RXI-2_RXI-2") (pintype "bidirectional"))
    )
    (net (code "121") (name "unconnected-(U$2-PadRXO-1)") (class "Default")
      (node (ref "U$2") (pin "RXO-1") (pinfunction "RXO-1_RXO-1") (pintype "bidirectional"))
    )
    (net (code "122") (name "unconnected-(U$2-PadRXO-2)") (class "Default")
      (node (ref "U$2") (pin "RXO-2") (pinfunction "RXO-2_RXO-2") (pintype "bidirectional"))
    )
    (net (code "123") (name "unconnected-(U$2-PadTXI-2)") (class "Default")
      (node (ref "U$2") (pin "TXI-2") (pinfunction "TXI-2_TXI-2") (pintype "bidirectional"))
    )
    (net (code "124") (name "unconnected-(U$2-PadTXO-2)") (class "Default")
      (node (ref "U$2") (pin "TXO-2") (pinfunction "TXO-2_TXO-2") (pintype "bidirectional"))
    )
    (net (code "125") (name "unconnected-(USB_RASP-Pad2)") (class "Default")
      (node (ref "USB_RASP") (pin "2") (pinfunction "2_2") (pintype "passive"))
    )
    (net (code "126") (name "unconnected-(USB_RASP-Pad3)") (class "Default")
      (node (ref "USB_RASP") (pin "3") (pinfunction "3_3") (pintype "passive"))
    )
  )
)
